# SCH_Visualizer_2026-05-25.net
KiCad netlist of a schematic drawn in EasyEDA
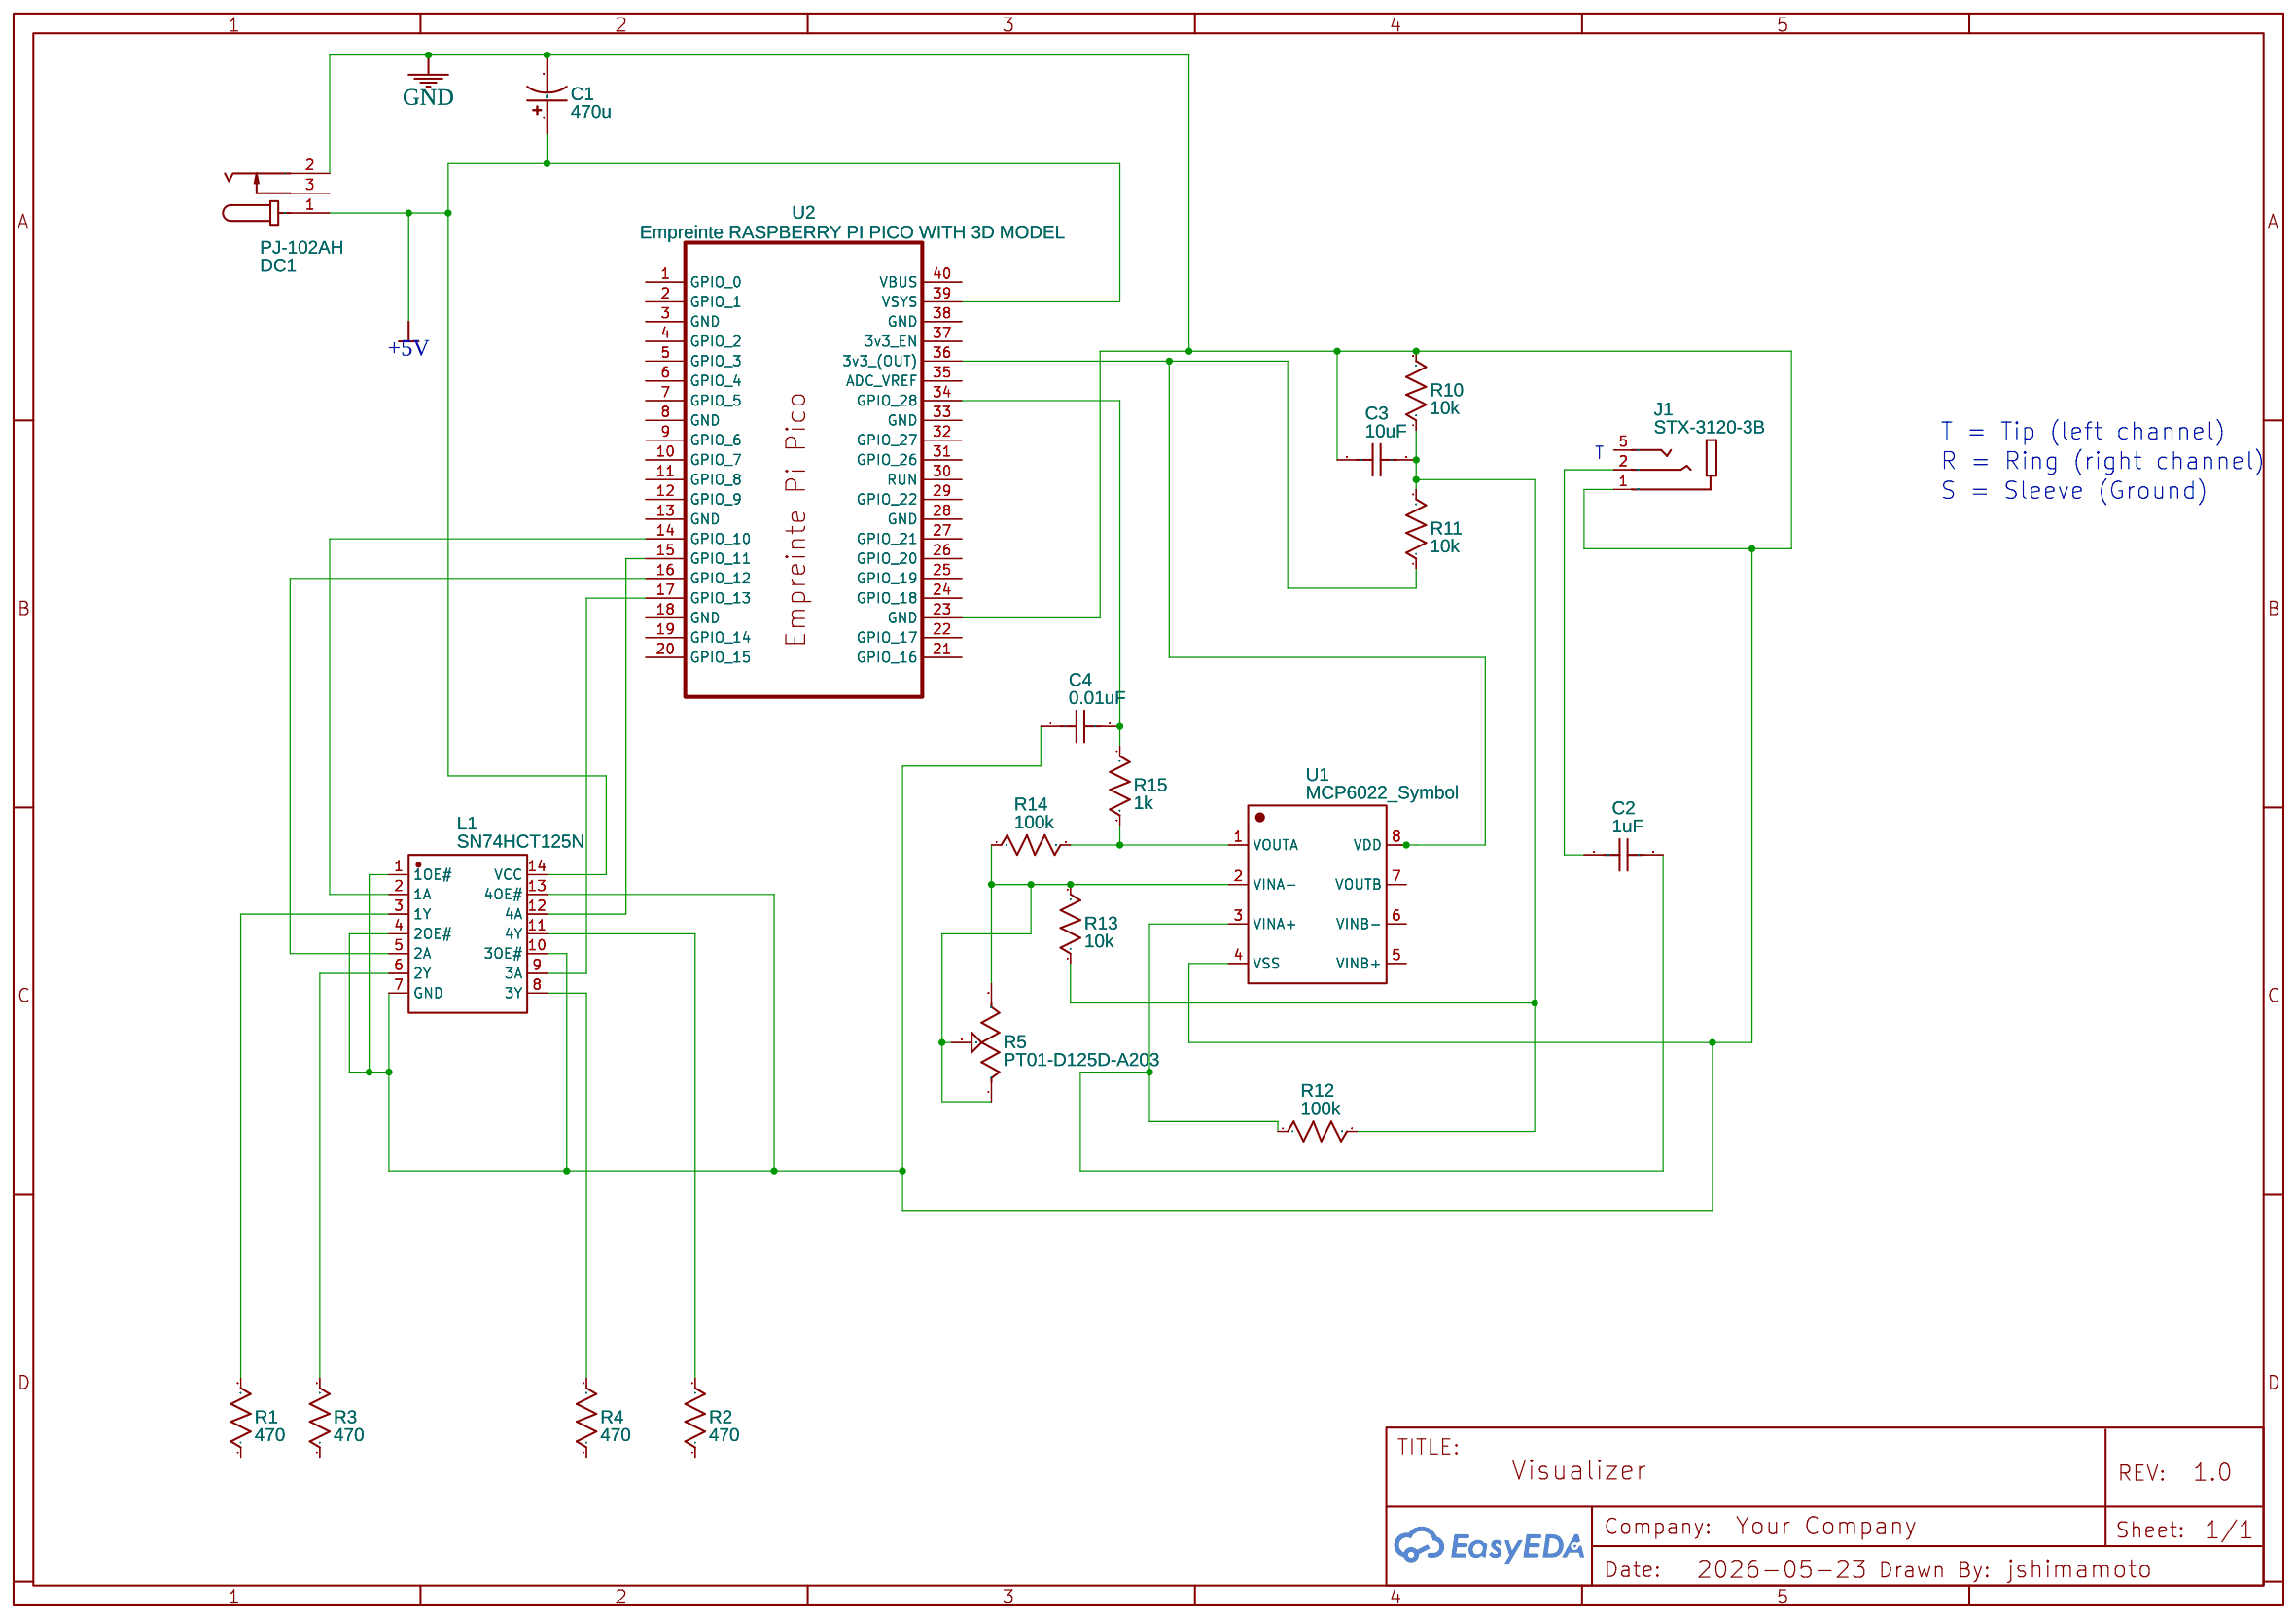
[diagram p0: schematic sheet]

(export (version "E")
  (design (tool "Eeschema 10.0.6"))
  (components
    (comp (ref "C1") (value "470u") (libsource (lib "") (part "C_Tan_SMD_A_US")))
    (comp (ref "C2") (value "1uF") (libsource (lib "") (part "C_0603_US")))
    (comp (ref "C3") (value "10uF") (libsource (lib "") (part "C_0603_US")))
    (comp (ref "C4") (value "0.01uF") (libsource (lib "") (part "C_0603_US")))
    (comp (ref "DC1")
      (value "PJ-102AH")
      (fields (field (name "Manufacturer") "CUI Devices"))
      (libsource (lib "") (part "PJ-102AH"))
    )
    (comp (ref "J1") (value "STX-3120-3B") (libsource (lib "") (part "STX-3120-3B")))
    (comp (ref "L1")
      (value "SN74HCT125N")
      (fields (field (name "Manufacturer") "TI(德州仪器)"))
      (libsource (lib "") (part "SN74HCT125N"))
    )
    (comp (ref "R1") (value "470") (libsource (lib "") (part "R_0603_US_1")))
    (comp (ref "R2") (value "470") (libsource (lib "") (part "R_0603_US_1")))
    (comp (ref "R3") (value "470") (libsource (lib "") (part "R_0603_US_1")))
    (comp (ref "R4") (value "470") (libsource (lib "") (part "R_0603_US_1")))
    (comp (ref "R5") (value "PT01-D125D-A203") (libsource (lib "") (part "PT01-D125D-A203")))
    (comp (ref "R10") (value "10k") (libsource (lib "") (part "R_0603_US_1")))
    (comp (ref "R11") (value "10k") (libsource (lib "") (part "R_0603_US_1")))
    (comp (ref "R12") (value "100k") (libsource (lib "") (part "R_0603_US_2")))
    (comp (ref "R13") (value "10k") (libsource (lib "") (part "R_0603_US_1")))
    (comp (ref "R14") (value "100k") (libsource (lib "") (part "R_0603_US_2")))
    (comp (ref "R15") (value "1k") (libsource (lib "") (part "R_0603_US")))
    (comp (ref "U1") (value "MCP6022_Symbol") (libsource (lib "") (part "MCP6022_Symbol")))
    (comp (ref "U2")
      (value "Empreinte RASPBERRY PI PICO WITH 3D MODEL")
      (libsource (lib "") (part "Empreinte RASPBERRY PI PICO WITH 3D MODEL"))
    )
  )
  (nets
    (net (code "1") (name "+5V") (class "Default")
      (node (ref "C1") (pin "1") (pinfunction "1_1") (pintype "unspecified"))
      (node (ref "DC1") (pin "1") (pinfunction "1_1") (pintype "unspecified"))
      (node (ref "L1") (pin "14") (pinfunction "VCC_14") (pintype "unspecified"))
      (node (ref "U2") (pin "39") (pinfunction "VSYS_39") (pintype "unspecified"))
    )
    (net (code "2") (name "GND") (class "Default")
      (node (ref "C1") (pin "2") (pinfunction "2_2") (pintype "unspecified"))
      (node (ref "C3") (pin "1") (pinfunction "1_1") (pintype "unspecified"))
      (node (ref "C4") (pin "1") (pinfunction "1_1") (pintype "unspecified"))
      (node (ref "DC1") (pin "2") (pinfunction "2_2") (pintype "unspecified"))
      (node (ref "J1") (pin "1") (pinfunction "SLEEVE_1") (pintype "bidirectional"))
      (node (ref "L1") (pin "1") (pinfunction "1OE#_1") (pintype "unspecified"))
      (node (ref "L1") (pin "10") (pinfunction "3OE#_10") (pintype "unspecified"))
      (node (ref "L1") (pin "13") (pinfunction "4OE#_13") (pintype "unspecified"))
      (node (ref "L1") (pin "4") (pinfunction "2OE#_4") (pintype "unspecified"))
      (node (ref "L1") (pin "7") (pinfunction "GND_7") (pintype "unspecified"))
      (node (ref "R10") (pin "2") (pinfunction "2_2") (pintype "unspecified"))
      (node (ref "U1") (pin "4") (pinfunction "VSS_4") (pintype "unspecified"))
      (node (ref "U2") (pin "23") (pinfunction "GND_23") (pintype "unspecified"))
    )
    (net (code "3") (name "Net-(C3-Pad2)") (class "Default")
      (node (ref "C3") (pin "2") (pinfunction "2_2") (pintype "unspecified"))
      (node (ref "R10") (pin "1") (pinfunction "1_1") (pintype "unspecified"))
      (node (ref "R11") (pin "2") (pinfunction "2_2") (pintype "unspecified"))
      (node (ref "R12") (pin "2") (pinfunction "2_2") (pintype "unspecified"))
      (node (ref "R13") (pin "1") (pinfunction "1_1") (pintype "unspecified"))
    )
    (net (code "4") (name "Net-(J1-RING)") (class "Default")
      (node (ref "C2") (pin "1") (pinfunction "1_1") (pintype "unspecified"))
      (node (ref "J1") (pin "2") (pinfunction "RING_2") (pintype "bidirectional"))
    )
    (net (code "5") (name "Net-(L1-1A)") (class "Default")
      (node (ref "L1") (pin "2") (pinfunction "1A_2") (pintype "unspecified"))
      (node (ref "U2") (pin "14") (pinfunction "GPIO_10_14") (pintype "unspecified"))
    )
    (net (code "6") (name "Net-(L1-1Y)") (class "Default")
      (node (ref "L1") (pin "3") (pinfunction "1Y_3") (pintype "unspecified"))
      (node (ref "R1") (pin "2") (pinfunction "2_2") (pintype "unspecified"))
    )
    (net (code "7") (name "Net-(L1-2A)") (class "Default")
      (node (ref "L1") (pin "5") (pinfunction "2A_5") (pintype "unspecified"))
      (node (ref "U2") (pin "16") (pinfunction "GPIO_12_16") (pintype "unspecified"))
    )
    (net (code "8") (name "Net-(L1-2Y)") (class "Default")
      (node (ref "L1") (pin "6") (pinfunction "2Y_6") (pintype "unspecified"))
      (node (ref "R3") (pin "2") (pinfunction "2_2") (pintype "unspecified"))
    )
    (net (code "9") (name "Net-(L1-3A)") (class "Default")
      (node (ref "L1") (pin "9") (pinfunction "3A_9") (pintype "unspecified"))
      (node (ref "U2") (pin "17") (pinfunction "GPIO_13_17") (pintype "unspecified"))
    )
    (net (code "10") (name "Net-(L1-3Y)") (class "Default")
      (node (ref "L1") (pin "8") (pinfunction "3Y_8") (pintype "unspecified"))
      (node (ref "R4") (pin "2") (pinfunction "2_2") (pintype "unspecified"))
    )
    (net (code "11") (name "Net-(L1-4A)") (class "Default")
      (node (ref "L1") (pin "12") (pinfunction "4A_12") (pintype "unspecified"))
      (node (ref "U2") (pin "15") (pinfunction "GPIO_11_15") (pintype "unspecified"))
    )
    (net (code "12") (name "Net-(L1-4Y)") (class "Default")
      (node (ref "L1") (pin "11") (pinfunction "4Y_11") (pintype "unspecified"))
      (node (ref "R2") (pin "2") (pinfunction "2_2") (pintype "unspecified"))
    )
    (net (code "13") (name "Net-(U1-VDD)") (class "Default")
      (node (ref "R11") (pin "1") (pinfunction "1_1") (pintype "unspecified"))
      (node (ref "U1") (pin "8") (pinfunction "VDD_8") (pintype "unspecified"))
      (node (ref "U2") (pin "36") (pinfunction "3v3_(OUT)_36") (pintype "unspecified"))
    )
    (net (code "14") (name "Net-(U1-VINA+)") (class "Default")
      (node (ref "C2") (pin "2") (pinfunction "2_2") (pintype "unspecified"))
      (node (ref "R12") (pin "1") (pinfunction "1_1") (pintype "unspecified"))
      (node (ref "U1") (pin "3") (pinfunction "VINA+_3") (pintype "unspecified"))
    )
    (net (code "15") (name "Net-(U1-VINA-)") (class "Default")
      (node (ref "R13") (pin "2") (pinfunction "2_2") (pintype "unspecified"))
      (node (ref "R14") (pin "1") (pinfunction "1_1") (pintype "unspecified"))
      (node (ref "R5") (pin "1") (pinfunction "1_1") (pintype "bidirectional"))
      (node (ref "R5") (pin "2") (pinfunction "2_2") (pintype "bidirectional"))
      (node (ref "R5") (pin "3") (pinfunction "3_3") (pintype "bidirectional"))
      (node (ref "U1") (pin "2") (pinfunction "VINA-_2") (pintype "unspecified"))
    )
    (net (code "16") (name "Net-(U1-VOUTA)") (class "Default")
      (node (ref "R14") (pin "2") (pinfunction "2_2") (pintype "unspecified"))
      (node (ref "R15") (pin "2") (pinfunction "2_2") (pintype "unspecified"))
      (node (ref "U1") (pin "1") (pinfunction "VOUTA_1") (pintype "unspecified"))
    )
    (net (code "17") (name "Net-(U2-GPIO_28)") (class "Default")
      (node (ref "C4") (pin "2") (pinfunction "2_2") (pintype "unspecified"))
      (node (ref "R15") (pin "1") (pinfunction "1_1") (pintype "unspecified"))
      (node (ref "U2") (pin "34") (pinfunction "GPIO_28_34") (pintype "unspecified"))
    )
    (net (code "18") (name "unconnected-(DC1-Pad3)") (class "Default")
      (node (ref "DC1") (pin "3") (pinfunction "3_3") (pintype "unspecified"))
    )
    (net (code "19") (name "unconnected-(J1-TIP-Pad5)") (class "Default")
      (node (ref "J1") (pin "5") (pinfunction "TIP_5") (pintype "bidirectional"))
    )
    (net (code "20") (name "unconnected-(R1-Pad1)") (class "Default")
      (node (ref "R1") (pin "1") (pinfunction "1_1") (pintype "unspecified"))
    )
    (net (code "21") (name "unconnected-(R2-Pad1)") (class "Default")
      (node (ref "R2") (pin "1") (pinfunction "1_1") (pintype "unspecified"))
    )
    (net (code "22") (name "unconnected-(R3-Pad1)") (class "Default")
      (node (ref "R3") (pin "1") (pinfunction "1_1") (pintype "unspecified"))
    )
    (net (code "23") (name "unconnected-(R4-Pad1)") (class "Default")
      (node (ref "R4") (pin "1") (pinfunction "1_1") (pintype "unspecified"))
    )
    (net (code "24") (name "unconnected-(U1-VINB+-Pad5)") (class "Default")
      (node (ref "U1") (pin "5") (pinfunction "VINB+_5") (pintype "unspecified"))
    )
    (net (code "25") (name "unconnected-(U1-VINB--Pad6)") (class "Default")
      (node (ref "U1") (pin "6") (pinfunction "VINB-_6") (pintype "unspecified"))
    )
    (net (code "26") (name "unconnected-(U1-VOUTB-Pad7)") (class "Default")
      (node (ref "U1") (pin "7") (pinfunction "VOUTB_7") (pintype "unspecified"))
    )
    (net (code "27") (name "unconnected-(U2-3v3_EN-Pad37)") (class "Default")
      (node (ref "U2") (pin "37") (pinfunction "3v3_EN_37") (pintype "unspecified"))
    )
    (net (code "28") (name "unconnected-(U2-ADC_VREF-Pad35)") (class "Default")
      (node (ref "U2") (pin "35") (pinfunction "ADC_VREF_35") (pintype "unspecified"))
    )
    (net (code "29") (name "unconnected-(U2-GND-Pad3)") (class "Default")
      (node (ref "U2") (pin "3") (pinfunction "GND_3") (pintype "unspecified"))
    )
    (net (code "30") (name "unconnected-(U2-GND-Pad8)") (class "Default")
      (node (ref "U2") (pin "8") (pinfunction "GND_8") (pintype "unspecified"))
    )
    (net (code "31") (name "unconnected-(U2-GND-Pad13)") (class "Default")
      (node (ref "U2") (pin "13") (pinfunction "GND_13") (pintype "unspecified"))
    )
    (net (code "32") (name "unconnected-(U2-GND-Pad18)") (class "Default")
      (node (ref "U2") (pin "18") (pinfunction "GND_18") (pintype "unspecified"))
    )
    (net (code "33") (name "unconnected-(U2-GND-Pad28)") (class "Default")
      (node (ref "U2") (pin "28") (pinfunction "GND_28") (pintype "unspecified"))
    )
    (net (code "34") (name "unconnected-(U2-GND-Pad33)") (class "Default")
      (node (ref "U2") (pin "33") (pinfunction "GND_33") (pintype "unspecified"))
    )
    (net (code "35") (name "unconnected-(U2-GND-Pad38)") (class "Default")
      (node (ref "U2") (pin "38") (pinfunction "GND_38") (pintype "unspecified"))
    )
    (net (code "36") (name "unconnected-(U2-GPIO_0-Pad1)") (class "Default")
      (node (ref "U2") (pin "1") (pinfunction "GPIO_0_1") (pintype "unspecified"))
    )
    (net (code "37") (name "unconnected-(U2-GPIO_1-Pad2)") (class "Default")
      (node (ref "U2") (pin "2") (pinfunction "GPIO_1_2") (pintype "unspecified"))
    )
    (net (code "38") (name "unconnected-(U2-GPIO_2-Pad4)") (class "Default")
      (node (ref "U2") (pin "4") (pinfunction "GPIO_2_4") (pintype "unspecified"))
    )
    (net (code "39") (name "unconnected-(U2-GPIO_3-Pad5)") (class "Default")
      (node (ref "U2") (pin "5") (pinfunction "GPIO_3_5") (pintype "unspecified"))
    )
    (net (code "40") (name "unconnected-(U2-GPIO_4-Pad6)") (class "Default")
      (node (ref "U2") (pin "6") (pinfunction "GPIO_4_6") (pintype "unspecified"))
    )
    (net (code "41") (name "unconnected-(U2-GPIO_5-Pad7)") (class "Default")
      (node (ref "U2") (pin "7") (pinfunction "GPIO_5_7") (pintype "unspecified"))
    )
    (net (code "42") (name "unconnected-(U2-GPIO_6-Pad9)") (class "Default")
      (node (ref "U2") (pin "9") (pinfunction "GPIO_6_9") (pintype "unspecified"))
    )
    (net (code "43") (name "unconnected-(U2-GPIO_7-Pad10)") (class "Default")
      (node (ref "U2") (pin "10") (pinfunction "GPIO_7_10") (pintype "unspecified"))
    )
    (net (code "44") (name "unconnected-(U2-GPIO_8-Pad11)") (class "Default")
      (node (ref "U2") (pin "11") (pinfunction "GPIO_8_11") (pintype "unspecified"))
    )
    (net (code "45") (name "unconnected-(U2-GPIO_9-Pad12)") (class "Default")
      (node (ref "U2") (pin "12") (pinfunction "GPIO_9_12") (pintype "unspecified"))
    )
    (net (code "46") (name "unconnected-(U2-GPIO_14-Pad19)") (class "Default")
      (node (ref "U2") (pin "19") (pinfunction "GPIO_14_19") (pintype "unspecified"))
    )
    (net (code "47") (name "unconnected-(U2-GPIO_15-Pad20)") (class "Default")
      (node (ref "U2") (pin "20") (pinfunction "GPIO_15_20") (pintype "unspecified"))
    )
    (net (code "48") (name "unconnected-(U2-GPIO_16-Pad21)") (class "Default")
      (node (ref "U2") (pin "21") (pinfunction "GPIO_16_21") (pintype "unspecified"))
    )
    (net (code "49") (name "unconnected-(U2-GPIO_17-Pad22)") (class "Default")
      (node (ref "U2") (pin "22") (pinfunction "GPIO_17_22") (pintype "unspecified"))
    )
    (net (code "50") (name "unconnected-(U2-GPIO_18-Pad24)") (class "Default")
      (node (ref "U2") (pin "24") (pinfunction "GPIO_18_24") (pintype "unspecified"))
    )
    (net (code "51") (name "unconnected-(U2-GPIO_19-Pad25)") (class "Default")
      (node (ref "U2") (pin "25") (pinfunction "GPIO_19_25") (pintype "unspecified"))
    )
    (net (code "52") (name "unconnected-(U2-GPIO_20-Pad26)") (class "Default")
      (node (ref "U2") (pin "26") (pinfunction "GPIO_20_26") (pintype "unspecified"))
    )
    (net (code "53") (name "unconnected-(U2-GPIO_21-Pad27)") (class "Default")
      (node (ref "U2") (pin "27") (pinfunction "GPIO_21_27") (pintype "unspecified"))
    )
    (net (code "54") (name "unconnected-(U2-GPIO_22-Pad29)") (class "Default")
      (node (ref "U2") (pin "29") (pinfunction "GPIO_22_29") (pintype "unspecified"))
    )
    (net (code "55") (name "unconnected-(U2-GPIO_26-Pad31)") (class "Default")
      (node (ref "U2") (pin "31") (pinfunction "GPIO_26_31") (pintype "unspecified"))
    )
    (net (code "56") (name "unconnected-(U2-GPIO_27-Pad32)") (class "Default")
      (node (ref "U2") (pin "32") (pinfunction "GPIO_27_32") (pintype "unspecified"))
    )
    (net (code "57") (name "unconnected-(U2-RUN-Pad30)") (class "Default")
      (node (ref "U2") (pin "30") (pinfunction "RUN_30") (pintype "unspecified"))
    )
    (net (code "58") (name "unconnected-(U2-VBUS-Pad40)") (class "Default")
      (node (ref "U2") (pin "40") (pinfunction "VBUS_40") (pintype "unspecified"))
    )
  )
)
